# ItalyMap-10.net
KiCad netlist of a schematic drawn in EAGLE
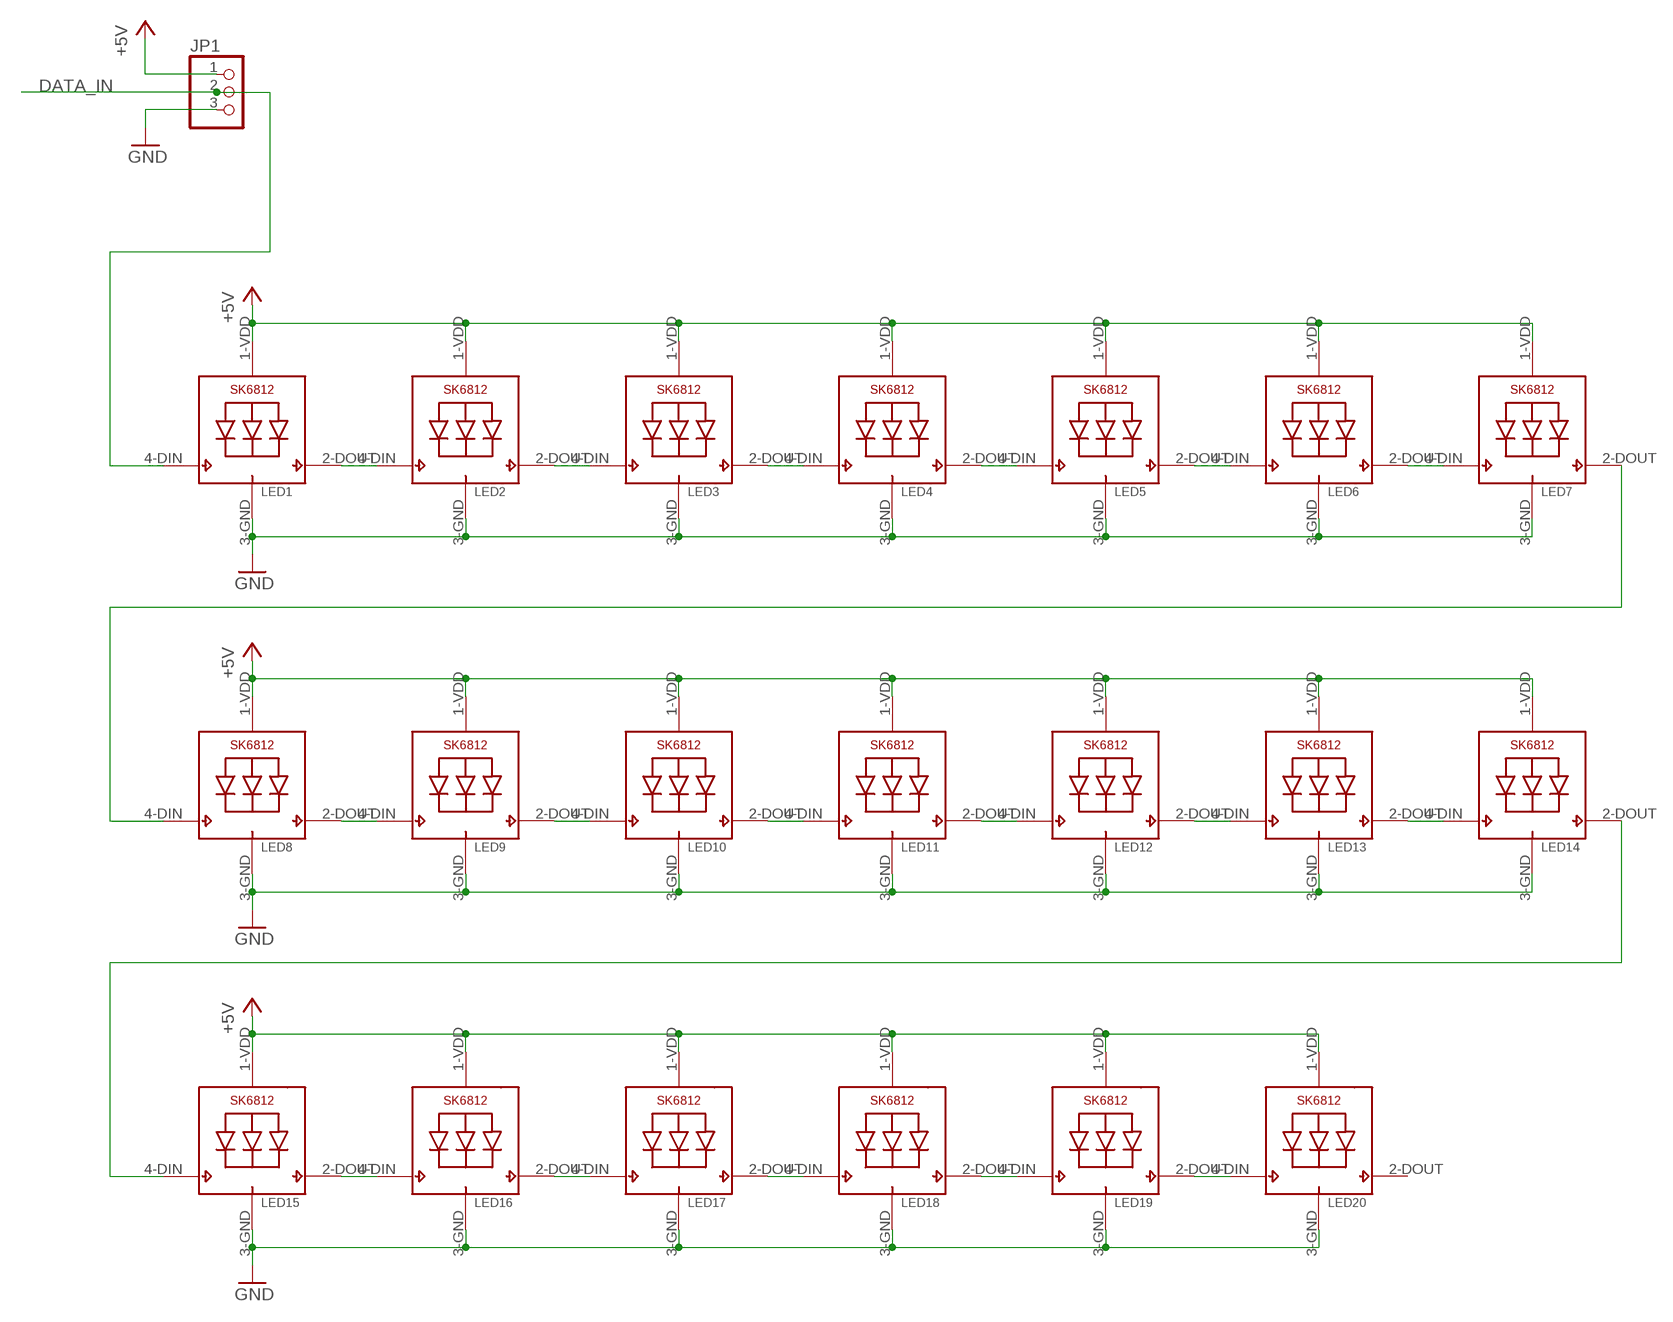
[diagram p0: schematic, sheet 1]

(export (version "E")
  (design (tool "Eeschema 10.0.6"))
  (components
    (comp (ref "JP1")
      (value "PINHD-1X3")
      (footprint "eagle-import:1X03")
      (libsource (lib "eagle-import") (part "PINHD-1X3"))
    )
    (comp (ref "LED1")
      (value "SK6812")
      (footprint "eagle-import:LED3228")
      (libsource (lib "eagle-import") (part "SK6812"))
    )
    (comp (ref "LED2")
      (value "SK6812")
      (footprint "eagle-import:LED3228")
      (libsource (lib "eagle-import") (part "SK6812"))
    )
    (comp (ref "LED3")
      (value "SK6812")
      (footprint "eagle-import:LED3228")
      (libsource (lib "eagle-import") (part "SK6812"))
    )
    (comp (ref "LED4")
      (value "SK6812")
      (footprint "eagle-import:LED3228")
      (libsource (lib "eagle-import") (part "SK6812"))
    )
    (comp (ref "LED5")
      (value "SK6812")
      (footprint "eagle-import:LED3228")
      (libsource (lib "eagle-import") (part "SK6812"))
    )
    (comp (ref "LED6")
      (value "SK6812")
      (footprint "eagle-import:LED3228")
      (libsource (lib "eagle-import") (part "SK6812"))
    )
    (comp (ref "LED7")
      (value "SK6812")
      (footprint "eagle-import:LED3228")
      (libsource (lib "eagle-import") (part "SK6812"))
    )
    (comp (ref "LED8")
      (value "SK6812")
      (footprint "eagle-import:LED3228")
      (libsource (lib "eagle-import") (part "SK6812"))
    )
    (comp (ref "LED9")
      (value "SK6812")
      (footprint "eagle-import:LED3228")
      (libsource (lib "eagle-import") (part "SK6812"))
    )
    (comp (ref "LED10")
      (value "SK6812")
      (footprint "eagle-import:LED3228")
      (libsource (lib "eagle-import") (part "SK6812"))
    )
    (comp (ref "LED11")
      (value "SK6812")
      (footprint "eagle-import:LED3228")
      (libsource (lib "eagle-import") (part "SK6812"))
    )
    (comp (ref "LED12")
      (value "SK6812")
      (footprint "eagle-import:LED3228")
      (libsource (lib "eagle-import") (part "SK6812"))
    )
    (comp (ref "LED13")
      (value "SK6812")
      (footprint "eagle-import:LED3228")
      (libsource (lib "eagle-import") (part "SK6812"))
    )
    (comp (ref "LED14")
      (value "SK6812")
      (footprint "eagle-import:LED3228")
      (libsource (lib "eagle-import") (part "SK6812"))
    )
    (comp (ref "LED15")
      (value "SK6812")
      (footprint "eagle-import:LED3228")
      (libsource (lib "eagle-import") (part "SK6812"))
    )
    (comp (ref "LED16")
      (value "SK6812")
      (footprint "eagle-import:LED3228")
      (libsource (lib "eagle-import") (part "SK6812"))
    )
    (comp (ref "LED17")
      (value "SK6812")
      (footprint "eagle-import:LED3228")
      (libsource (lib "eagle-import") (part "SK6812"))
    )
    (comp (ref "LED18")
      (value "SK6812")
      (footprint "eagle-import:LED3228")
      (libsource (lib "eagle-import") (part "SK6812"))
    )
    (comp (ref "LED19")
      (value "SK6812")
      (footprint "eagle-import:LED3228")
      (libsource (lib "eagle-import") (part "SK6812"))
    )
    (comp (ref "LED20")
      (value "SK6812")
      (footprint "eagle-import:LED3228")
      (libsource (lib "eagle-import") (part "SK6812"))
    )
  )
  (nets
    (net (code "1") (name "+5V") (class "Default")
      (node (ref "JP1") (pin "1") (pinfunction "1_1") (pintype "passive"))
      (node (ref "LED1") (pin "1-VDD") (pinfunction "VDD_1-VDD") (pintype "power_in"))
      (node (ref "LED10") (pin "1-VDD") (pinfunction "VDD_1-VDD") (pintype "power_in"))
      (node (ref "LED11") (pin "1-VDD") (pinfunction "VDD_1-VDD") (pintype "power_in"))
      (node (ref "LED12") (pin "1-VDD") (pinfunction "VDD_1-VDD") (pintype "power_in"))
      (node (ref "LED13") (pin "1-VDD") (pinfunction "VDD_1-VDD") (pintype "power_in"))
      (node (ref "LED14") (pin "1-VDD") (pinfunction "VDD_1-VDD") (pintype "power_in"))
      (node (ref "LED15") (pin "1-VDD") (pinfunction "VDD_1-VDD") (pintype "power_in"))
      (node (ref "LED16") (pin "1-VDD") (pinfunction "VDD_1-VDD") (pintype "power_in"))
      (node (ref "LED17") (pin "1-VDD") (pinfunction "VDD_1-VDD") (pintype "power_in"))
      (node (ref "LED18") (pin "1-VDD") (pinfunction "VDD_1-VDD") (pintype "power_in"))
      (node (ref "LED19") (pin "1-VDD") (pinfunction "VDD_1-VDD") (pintype "power_in"))
      (node (ref "LED2") (pin "1-VDD") (pinfunction "VDD_1-VDD") (pintype "power_in"))
      (node (ref "LED20") (pin "1-VDD") (pinfunction "VDD_1-VDD") (pintype "power_in"))
      (node (ref "LED3") (pin "1-VDD") (pinfunction "VDD_1-VDD") (pintype "power_in"))
      (node (ref "LED4") (pin "1-VDD") (pinfunction "VDD_1-VDD") (pintype "power_in"))
      (node (ref "LED5") (pin "1-VDD") (pinfunction "VDD_1-VDD") (pintype "power_in"))
      (node (ref "LED6") (pin "1-VDD") (pinfunction "VDD_1-VDD") (pintype "power_in"))
      (node (ref "LED7") (pin "1-VDD") (pinfunction "VDD_1-VDD") (pintype "power_in"))
      (node (ref "LED8") (pin "1-VDD") (pinfunction "VDD_1-VDD") (pintype "power_in"))
      (node (ref "LED9") (pin "1-VDD") (pinfunction "VDD_1-VDD") (pintype "power_in"))
    )
    (net (code "2") (name "/DATA_IN") (class "Default")
      (node (ref "JP1") (pin "2") (pinfunction "2_2") (pintype "passive"))
      (node (ref "LED1") (pin "4-DIN") (pinfunction "DI_4-DIN") (pintype "input"))
    )
    (net (code "3") (name "GND") (class "Default")
      (node (ref "JP1") (pin "3") (pinfunction "3_3") (pintype "passive"))
      (node (ref "LED1") (pin "3-GND") (pinfunction "GND_3-GND") (pintype "power_in"))
      (node (ref "LED10") (pin "3-GND") (pinfunction "GND_3-GND") (pintype "power_in"))
      (node (ref "LED11") (pin "3-GND") (pinfunction "GND_3-GND") (pintype "power_in"))
      (node (ref "LED12") (pin "3-GND") (pinfunction "GND_3-GND") (pintype "power_in"))
      (node (ref "LED13") (pin "3-GND") (pinfunction "GND_3-GND") (pintype "power_in"))
      (node (ref "LED14") (pin "3-GND") (pinfunction "GND_3-GND") (pintype "power_in"))
      (node (ref "LED15") (pin "3-GND") (pinfunction "GND_3-GND") (pintype "power_in"))
      (node (ref "LED16") (pin "3-GND") (pinfunction "GND_3-GND") (pintype "power_in"))
      (node (ref "LED17") (pin "3-GND") (pinfunction "GND_3-GND") (pintype "power_in"))
      (node (ref "LED18") (pin "3-GND") (pinfunction "GND_3-GND") (pintype "power_in"))
      (node (ref "LED19") (pin "3-GND") (pinfunction "GND_3-GND") (pintype "power_in"))
      (node (ref "LED2") (pin "3-GND") (pinfunction "GND_3-GND") (pintype "power_in"))
      (node (ref "LED20") (pin "3-GND") (pinfunction "GND_3-GND") (pintype "power_in"))
      (node (ref "LED3") (pin "3-GND") (pinfunction "GND_3-GND") (pintype "power_in"))
      (node (ref "LED4") (pin "3-GND") (pinfunction "GND_3-GND") (pintype "power_in"))
      (node (ref "LED5") (pin "3-GND") (pinfunction "GND_3-GND") (pintype "power_in"))
      (node (ref "LED6") (pin "3-GND") (pinfunction "GND_3-GND") (pintype "power_in"))
      (node (ref "LED7") (pin "3-GND") (pinfunction "GND_3-GND") (pintype "power_in"))
      (node (ref "LED8") (pin "3-GND") (pinfunction "GND_3-GND") (pintype "power_in"))
      (node (ref "LED9") (pin "3-GND") (pinfunction "GND_3-GND") (pintype "power_in"))
    )
    (net (code "4") (name "Net-(LED1-DO)") (class "Default")
      (node (ref "LED1") (pin "2-DOUT") (pinfunction "DO_2-DOUT") (pintype "output"))
      (node (ref "LED2") (pin "4-DIN") (pinfunction "DI_4-DIN") (pintype "input"))
    )
    (net (code "5") (name "Net-(LED2-DO)") (class "Default")
      (node (ref "LED2") (pin "2-DOUT") (pinfunction "DO_2-DOUT") (pintype "output"))
      (node (ref "LED3") (pin "4-DIN") (pinfunction "DI_4-DIN") (pintype "input"))
    )
    (net (code "6") (name "Net-(LED3-DO)") (class "Default")
      (node (ref "LED3") (pin "2-DOUT") (pinfunction "DO_2-DOUT") (pintype "output"))
      (node (ref "LED4") (pin "4-DIN") (pinfunction "DI_4-DIN") (pintype "input"))
    )
    (net (code "7") (name "Net-(LED4-DO)") (class "Default")
      (node (ref "LED4") (pin "2-DOUT") (pinfunction "DO_2-DOUT") (pintype "output"))
      (node (ref "LED5") (pin "4-DIN") (pinfunction "DI_4-DIN") (pintype "input"))
    )
    (net (code "8") (name "Net-(LED5-DO)") (class "Default")
      (node (ref "LED5") (pin "2-DOUT") (pinfunction "DO_2-DOUT") (pintype "output"))
      (node (ref "LED6") (pin "4-DIN") (pinfunction "DI_4-DIN") (pintype "input"))
    )
    (net (code "9") (name "Net-(LED6-DO)") (class "Default")
      (node (ref "LED6") (pin "2-DOUT") (pinfunction "DO_2-DOUT") (pintype "output"))
      (node (ref "LED7") (pin "4-DIN") (pinfunction "DI_4-DIN") (pintype "input"))
    )
    (net (code "10") (name "Net-(LED7-DO)") (class "Default")
      (node (ref "LED7") (pin "2-DOUT") (pinfunction "DO_2-DOUT") (pintype "output"))
      (node (ref "LED8") (pin "4-DIN") (pinfunction "DI_4-DIN") (pintype "input"))
    )
    (net (code "11") (name "Net-(LED8-DO)") (class "Default")
      (node (ref "LED8") (pin "2-DOUT") (pinfunction "DO_2-DOUT") (pintype "output"))
      (node (ref "LED9") (pin "4-DIN") (pinfunction "DI_4-DIN") (pintype "input"))
    )
    (net (code "12") (name "Net-(LED10-DI)") (class "Default")
      (node (ref "LED10") (pin "4-DIN") (pinfunction "DI_4-DIN") (pintype "input"))
      (node (ref "LED9") (pin "2-DOUT") (pinfunction "DO_2-DOUT") (pintype "output"))
    )
    (net (code "13") (name "Net-(LED10-DO)") (class "Default")
      (node (ref "LED10") (pin "2-DOUT") (pinfunction "DO_2-DOUT") (pintype "output"))
      (node (ref "LED11") (pin "4-DIN") (pinfunction "DI_4-DIN") (pintype "input"))
    )
    (net (code "14") (name "Net-(LED11-DO)") (class "Default")
      (node (ref "LED11") (pin "2-DOUT") (pinfunction "DO_2-DOUT") (pintype "output"))
      (node (ref "LED12") (pin "4-DIN") (pinfunction "DI_4-DIN") (pintype "input"))
    )
    (net (code "15") (name "Net-(LED12-DO)") (class "Default")
      (node (ref "LED12") (pin "2-DOUT") (pinfunction "DO_2-DOUT") (pintype "output"))
      (node (ref "LED13") (pin "4-DIN") (pinfunction "DI_4-DIN") (pintype "input"))
    )
    (net (code "16") (name "Net-(LED13-DO)") (class "Default")
      (node (ref "LED13") (pin "2-DOUT") (pinfunction "DO_2-DOUT") (pintype "output"))
      (node (ref "LED14") (pin "4-DIN") (pinfunction "DI_4-DIN") (pintype "input"))
    )
    (net (code "17") (name "Net-(LED14-DO)") (class "Default")
      (node (ref "LED14") (pin "2-DOUT") (pinfunction "DO_2-DOUT") (pintype "output"))
      (node (ref "LED15") (pin "4-DIN") (pinfunction "DI_4-DIN") (pintype "input"))
    )
    (net (code "18") (name "Net-(LED15-DO)") (class "Default")
      (node (ref "LED15") (pin "2-DOUT") (pinfunction "DO_2-DOUT") (pintype "output"))
      (node (ref "LED16") (pin "4-DIN") (pinfunction "DI_4-DIN") (pintype "input"))
    )
    (net (code "19") (name "Net-(LED16-DO)") (class "Default")
      (node (ref "LED16") (pin "2-DOUT") (pinfunction "DO_2-DOUT") (pintype "output"))
      (node (ref "LED17") (pin "4-DIN") (pinfunction "DI_4-DIN") (pintype "input"))
    )
    (net (code "20") (name "Net-(LED17-DO)") (class "Default")
      (node (ref "LED17") (pin "2-DOUT") (pinfunction "DO_2-DOUT") (pintype "output"))
      (node (ref "LED18") (pin "4-DIN") (pinfunction "DI_4-DIN") (pintype "input"))
    )
    (net (code "21") (name "Net-(LED18-DO)") (class "Default")
      (node (ref "LED18") (pin "2-DOUT") (pinfunction "DO_2-DOUT") (pintype "output"))
      (node (ref "LED19") (pin "4-DIN") (pinfunction "DI_4-DIN") (pintype "input"))
    )
    (net (code "22") (name "Net-(LED19-DO)") (class "Default")
      (node (ref "LED19") (pin "2-DOUT") (pinfunction "DO_2-DOUT") (pintype "output"))
      (node (ref "LED20") (pin "4-DIN") (pinfunction "DI_4-DIN") (pintype "input"))
    )
    (net (code "23") (name "unconnected-(LED20-DO-Pad2-DOUT)") (class "Default")
      (node (ref "LED20") (pin "2-DOUT") (pinfunction "DO_2-DOUT") (pintype "output"))
    )
  )
)
